# Power.net
KiCad netlist of a schematic drawn in Altium Designer
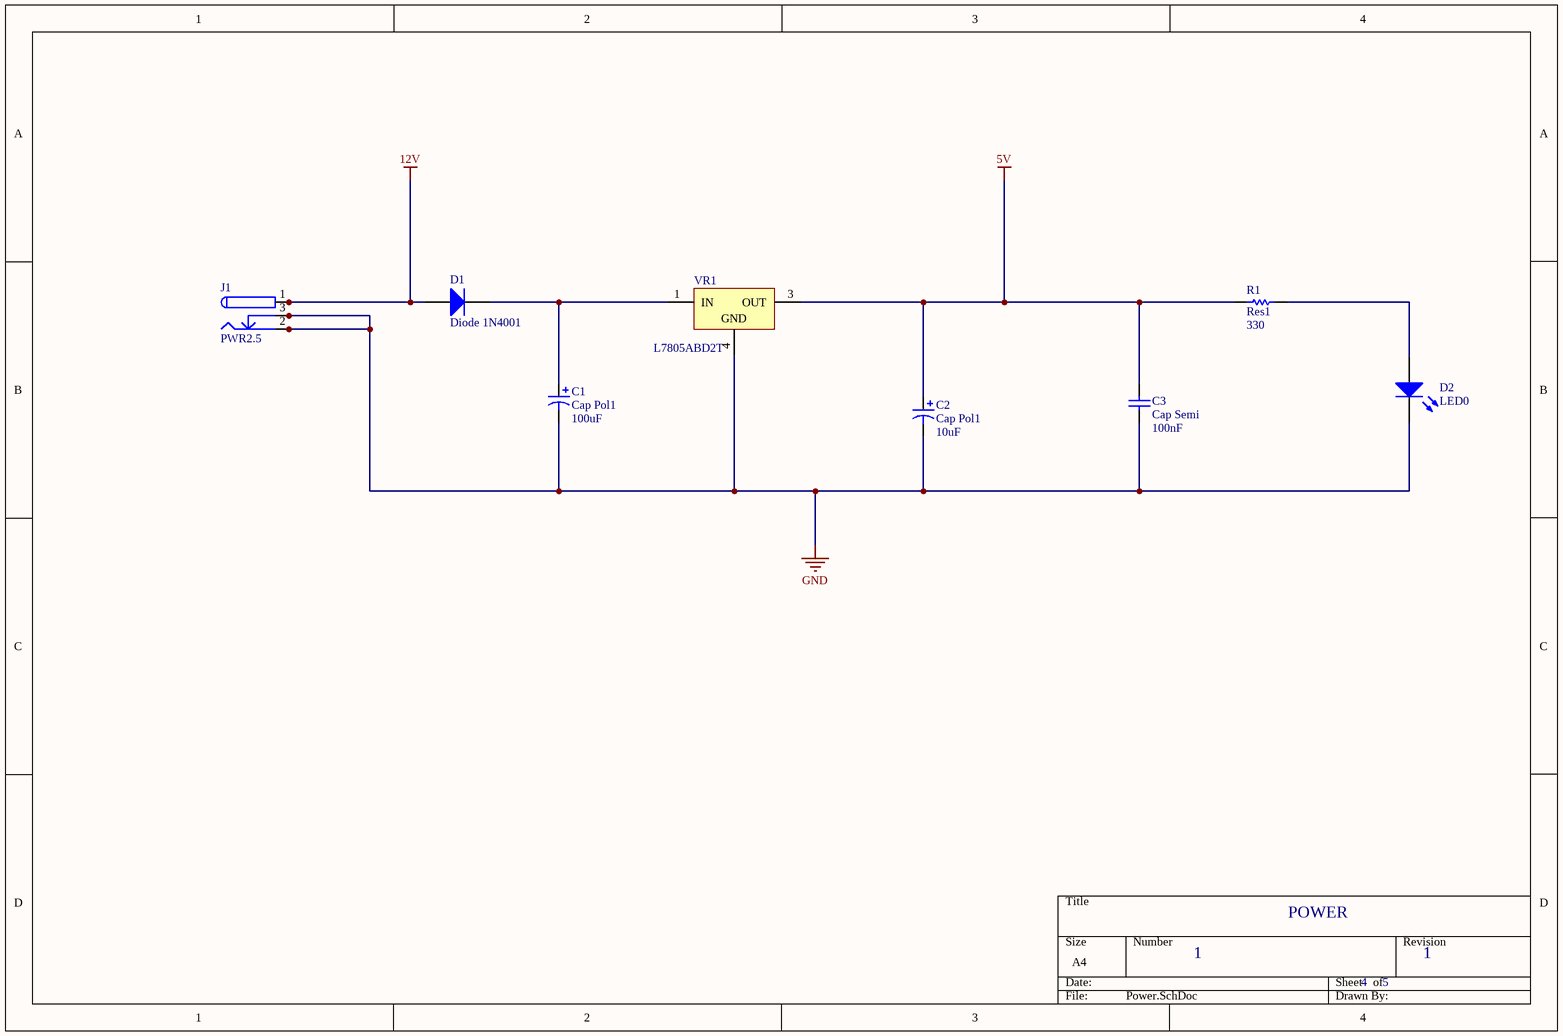
[diagram p0: Power.SchDoc]

(export (version "E")
  (design (tool "Eeschema 10.0.6"))
  (components
    (comp (ref "C1")
      (value "Cap Pol1")
      (footprint "RB7.6-15")
      (description "Polarized Capacitor (Radial)")
      (fields (field (name "ALTIUM_VALUE") "100uF") (field (name "PUBLISHER") "Altium Limited"))
      (libsource (lib "Miscellaneous Devices") (part "Cap Pol1"))
    )
    (comp (ref "C2")
      (value "Cap Pol1")
      (footprint "RB7.6-15")
      (description "Polarized Capacitor (Radial)")
      (fields (field (name "ALTIUM_VALUE") "10uF") (field (name "PUBLISHER") "Altium Limited"))
      (libsource (lib "Miscellaneous Devices") (part "Cap Pol1"))
    )
    (comp (ref "C3")
      (value "Cap Semi")
      (footprint "C1206")
      (description "Capacitor (Semiconductor SIM Model)")
      (fields (field (name "ALTIUM_VALUE") "100nF") (field (name "PUBLISHER") "Altium Limited"))
      (libsource (lib "Miscellaneous Devices") (part "Cap Semi"))
    )
    (comp (ref "D1")
      (value "Diode 1N4001")
      (footprint "DO-41")
      (description "1 Amp General Purpose Rectifier")
      (fields (field (name "PUBLISHER") "Altium Limited"))
      (libsource (lib "Miscellaneous Devices") (part "Diode 1N4001"))
    )
    (comp (ref "D2")
      (value "LED0")
      (footprint "LED-0")
      (description "Typical INFRARED GaAs LED")
      (fields (field (name "PUBLISHER") "Altium Limited"))
      (libsource (lib "Miscellaneous Devices") (part "LED0"))
    )
    (comp (ref "J1")
      (value "PWR2.5")
      (footprint "KLD-0202")
      (description "Low Voltage Power Supply Connector")
      (fields (field (name "PUBLISHER") "Altium Limited"))
      (libsource (lib "Miscellaneous Connectors") (part "PWR2.5"))
    )
    (comp (ref "R1")
      (value "Res1")
      (footprint "0805")
      (description "Resistor")
      (fields (field (name "ALTIUM_VALUE") "330") (field (name "PUBLISHER") "Altium Limited"))
      (libsource (lib "Miscellaneous Devices") (part "Res1"))
    )
    (comp (ref "VR1")
      (value "L7805ABD2T")
      (footprint "TO-263")
      (description "Precision 1A Regulator")
      (fields (field (name "PUBLISHER") "Altium Limited"))
      (libsource (lib "ST Power Mgt Voltage Regulator") (part "L7805ABD2T"))
    )
  )
  (nets
    (net (code "1") (name "5V") (class "Default")
      (node (ref "C2") (pin "1") (pinfunction "1_1") (pintype "passive"))
      (node (ref "C3") (pin "2") (pinfunction "2_2") (pintype "passive"))
      (node (ref "R1") (pin "1") (pinfunction "1_1") (pintype "passive"))
      (node (ref "VR1") (pin "3") (pinfunction "OUT_3") (pintype "power_in"))
    )
    (net (code "2") (name "12V") (class "Default")
      (node (ref "D1") (pin "1") (pinfunction "A_1") (pintype "passive"))
      (node (ref "J1") (pin "1") (pinfunction "1_1") (pintype "power_in"))
      (node (ref "J1") (pin "1A") (pinfunction "1A_1A") (pintype "power_in"))
      (node (ref "J1") (pin "1B") (pinfunction "1B_1B") (pintype "power_in"))
    )
    (net (code "3") (name "GND") (class "Default")
      (node (ref "C1") (pin "2") (pinfunction "2_2") (pintype "passive"))
      (node (ref "C2") (pin "2") (pinfunction "2_2") (pintype "passive"))
      (node (ref "C3") (pin "1") (pinfunction "1_1") (pintype "passive"))
      (node (ref "D2") (pin "2") (pinfunction "K_2") (pintype "passive"))
      (node (ref "J1") (pin "2") (pinfunction "2_2") (pintype "power_in"))
      (node (ref "J1") (pin "2A") (pinfunction "2A_2A") (pintype "power_in"))
      (node (ref "J1") (pin "2B") (pinfunction "2B_2B") (pintype "power_in"))
      (node (ref "J1") (pin "3") (pinfunction "3_3") (pintype "power_in"))
      (node (ref "J1") (pin "3A") (pinfunction "3A_3A") (pintype "power_in"))
      (node (ref "J1") (pin "3B") (pinfunction "3B_3B") (pintype "power_in"))
      (node (ref "VR1") (pin "4") (pinfunction "GND_4") (pintype "power_in"))
    )
    (net (code "4") (name "Net-(D1-K)") (class "Default")
      (node (ref "C1") (pin "1") (pinfunction "1_1") (pintype "passive"))
      (node (ref "D1") (pin "2") (pinfunction "K_2") (pintype "passive"))
      (node (ref "VR1") (pin "1") (pinfunction "IN_1") (pintype "power_in"))
    )
    (net (code "5") (name "Net-(D2-A)") (class "Default")
      (node (ref "D2") (pin "1") (pinfunction "A_1") (pintype "passive"))
      (node (ref "R1") (pin "2") (pinfunction "2_2") (pintype "passive"))
    )
  )
)
